# PA-VHF_60W.net
KiCad netlist of a schematic drawn in Altium Designer
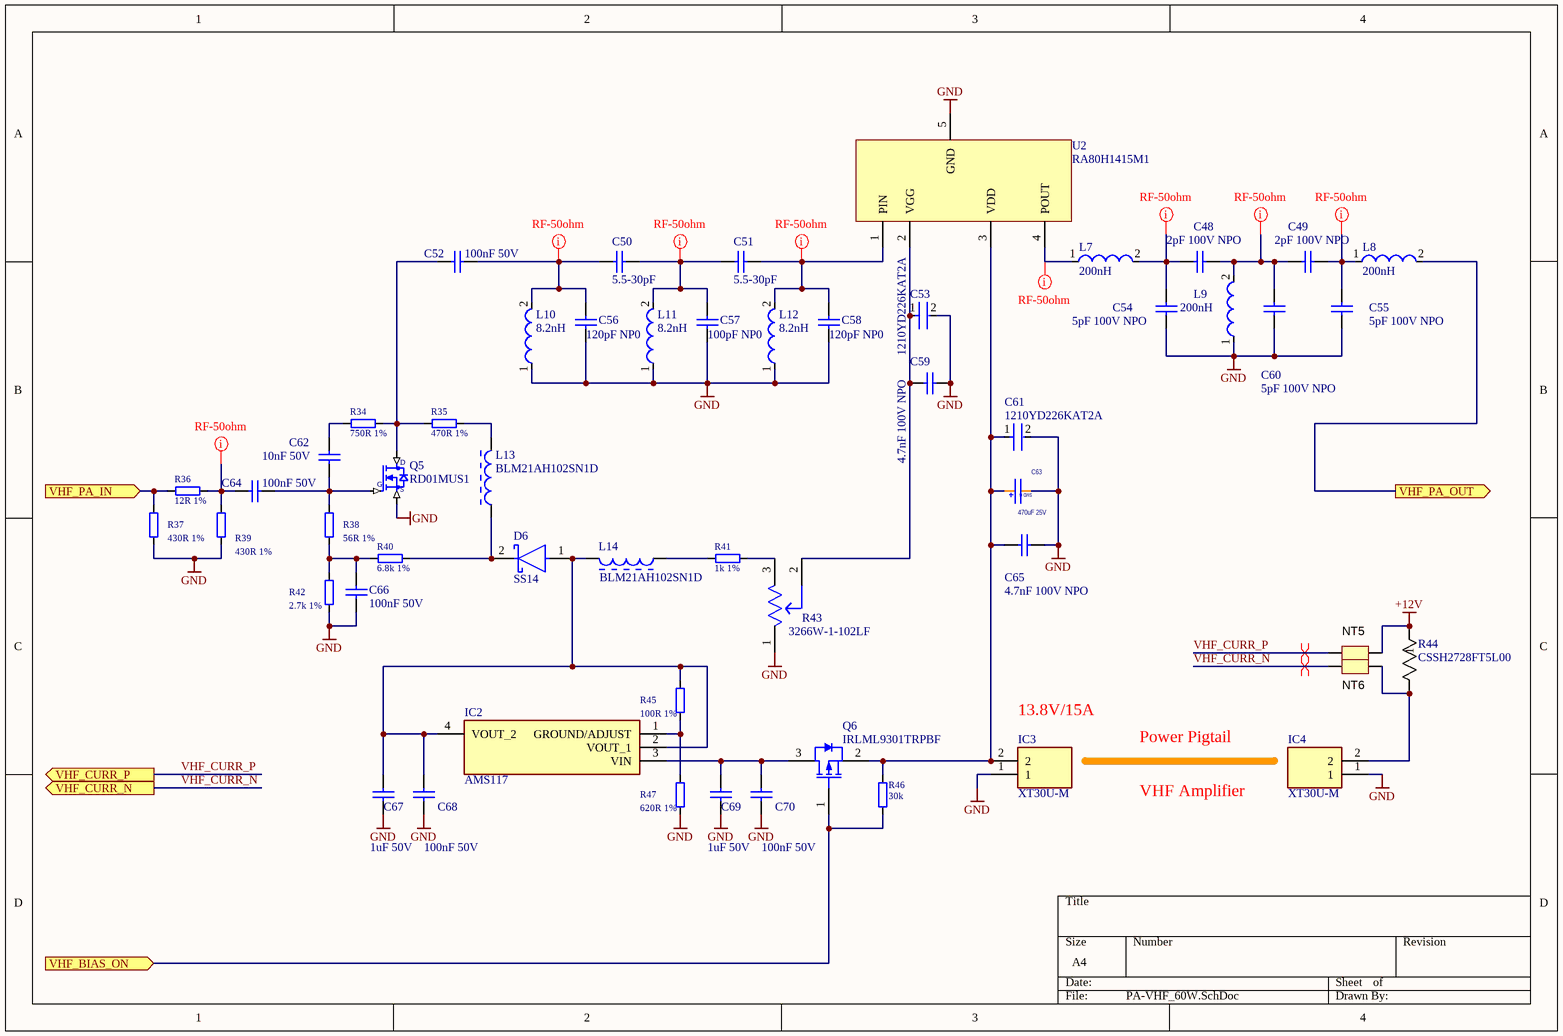
[diagram p0: PA-VHF_60W.SchDoc]

(export (version "E")
  (design (tool "Eeschema 10.0.6"))
  (components
    (comp (ref "C48")
      (value "2pF 100V NPO")
      (footprint "C-1206")
      (description "Ceramic Multilayer Capacitor")
      (libsource (lib "Hristo") (part "C semi"))
    )
    (comp (ref "C49")
      (value "2pF 100V NPO")
      (footprint "C-1206")
      (description "Ceramic Multilayer Capacitor")
      (libsource (lib "Hristo") (part "C semi"))
    )
    (comp (ref "C50")
      (value "5.5-30pF")
      (footprint "CAP-ADJ-SMD_L4.5-W3.2-L")
      (description "Ceramic Multilayer Capacitor")
      (fields (field (name "MANUFACTURER") "Yageo/Phycomp") (field (name "TOLERANCE") "±10%"))
      (libsource (lib "Hristo") (part "C semi"))
    )
    (comp (ref "C51")
      (value "5.5-30pF")
      (footprint "CAP-ADJ-SMD_L4.5-W3.2-L")
      (description "Ceramic Multilayer Capacitor")
      (fields (field (name "MANUFACTURER") "Yageo/Phycomp") (field (name "TOLERANCE") "±10%"))
      (libsource (lib "Hristo") (part "C semi"))
    )
    (comp (ref "C52")
      (value "100nF 50V")
      (footprint "C-0805")
      (description "Ceramic Multilayer Capacitor")
      (libsource (lib "Hristo") (part "C semi"))
    )
    (comp (ref "C53")
      (value "1210YD226KAT2A")
      (footprint "FP-1210-L_3_3_0_4-W_2_5_0-MFG")
      (description "General Purpose Ceramic Capacitor, 1210, 22uF, 10%, X5R, 15%, 16V")
      (fields (field (name "TOLERANCE") "10%") (field (name "VOLTAGE") "16V"))
      (libsource (lib "Altium Content Vault") (part "b4654b650e69147ec39a6b967a45e02"))
    )
    (comp (ref "C54")
      (value "5pF 100V NPO")
      (footprint "C-1206")
      (description "Ceramic Multilayer Capacitor")
      (libsource (lib "Hristo") (part "C semi"))
    )
    (comp (ref "C55")
      (value "5pF 100V NPO")
      (footprint "C-1206")
      (description "Ceramic Multilayer Capacitor")
      (libsource (lib "Hristo") (part "C semi"))
    )
    (comp (ref "C56")
      (value "120pF NP0")
      (footprint "C-0805")
      (description "Ceramic Multilayer Capacitor")
      (fields (field (name "MANUFACTURER") "Yageo/Phycomp") (field (name "TOLERANCE") "±10%"))
      (libsource (lib "Hristo") (part "C semi"))
    )
    (comp (ref "C57")
      (value "100pF NP0")
      (footprint "C-0805")
      (description "Ceramic Multilayer Capacitor")
      (fields (field (name "MANUFACTURER") "Yageo/Phycomp") (field (name "TOLERANCE") "±10%"))
      (libsource (lib "Hristo") (part "C semi"))
    )
    (comp (ref "C58")
      (value "120pF NP0")
      (footprint "C-0805")
      (description "Ceramic Multilayer Capacitor")
      (fields (field (name "MANUFACTURER") "Yageo/Phycomp") (field (name "TOLERANCE") "±10%"))
      (libsource (lib "Hristo") (part "C semi"))
    )
    (comp (ref "C59")
      (value "4.7nF 100V NPO")
      (footprint "C-1206")
      (description "Ceramic Multilayer Capacitor")
      (libsource (lib "Hristo") (part "C semi"))
    )
    (comp (ref "C60")
      (value "5pF 100V NPO")
      (footprint "C-1206")
      (description "Ceramic Multilayer Capacitor")
      (libsource (lib "Hristo") (part "C semi"))
    )
    (comp (ref "C61")
      (value "1210YD226KAT2A")
      (footprint "FP-1210-L_3_3_0_4-W_2_5_0-MFG")
      (description "General Purpose Ceramic Capacitor, 1210, 22uF, 10%, X5R, 15%, 16V")
      (fields (field (name "TOLERANCE") "10%") (field (name "VOLTAGE") "16V"))
      (libsource (lib "Altium Content Vault") (part "b4654b650e69147ec39a6b967a45e02"))
    )
    (comp (ref "C62")
      (value "10nF 50V")
      (footprint "C-0805")
      (description "Ceramic Multilayer Capacitor")
      (libsource (lib "Hristo") (part "C semi"))
    )
    (comp (ref "C63")
      (value "470uF 25V")
      (footprint "SMD-G-10X10.2")
      (description "CAP ALUM 470UF 20% 25V SMD")
      (fields
        (field (name "TOLERANCE") "±20 %")
        (field (name "VOLTAGE") "25V")
        (field (name "PUBLISHER") "Catcatcat Electronics")
      )
      (libsource (lib "CapacitorElectrolytic") (part "SMD-G 470uF 25V"))
    )
    (comp (ref "C64")
      (value "100nF 50V")
      (footprint "C-0805")
      (description "Ceramic Multilayer Capacitor")
      (libsource (lib "Hristo") (part "C semi"))
    )
    (comp (ref "C65")
      (value "4.7nF 100V NPO")
      (footprint "C-1206")
      (description "Ceramic Multilayer Capacitor")
      (libsource (lib "Hristo") (part "C semi"))
    )
    (comp (ref "C66")
      (value "100nF 50V")
      (footprint "C-0805")
      (description "Ceramic Multilayer Capacitor")
      (libsource (lib "Hristo") (part "C semi"))
    )
    (comp (ref "C67")
      (value "1uF 50V")
      (footprint "C-0805")
      (description "Ceramic Multilayer Capacitor")
      (libsource (lib "Hristo") (part "C semi"))
    )
    (comp (ref "C68")
      (value "100nF 50V")
      (footprint "C-0805")
      (description "Ceramic Multilayer Capacitor")
      (libsource (lib "Hristo") (part "C semi"))
    )
    (comp (ref "C69")
      (value "1uF 50V")
      (footprint "C-0805")
      (description "Ceramic Multilayer Capacitor")
      (libsource (lib "Hristo") (part "C semi"))
    )
    (comp (ref "C70")
      (value "100nF 50V")
      (footprint "C-0805")
      (description "Ceramic Multilayer Capacitor")
      (libsource (lib "Hristo") (part "C semi"))
    )
    (comp (ref "D6")
      (value "SS14")
      (footprint "FP-403AE-MFG")
      (description "DIODE SCHOTTKY 40V 1A SMA")
      (fields
        (field (name "MANUFACTURER") "ON Semiconductor")
        (field (name "OCTOPART") "https://octopart.com/ss14-on+semiconductor-29205033")
      )
      (libsource (lib "Altium Content Vault") (part "360ad2f4ac25a952324d13796385471"))
    )
    (comp (ref "IC2")
      (value "AMS117")
      (footprint "SamacSys:SOT229P700X180-4N")
      (description "Integrated Circuit")
      (libsource (lib "*") (part "AMS117"))
    )
    (comp (ref "IC3")
      (value "XT30U-M")
      (footprint "SamacSys:XT30UM")
      (description "Integrated Circuit")
      (libsource (lib "*") (part "XT30U-M"))
    )
    (comp (ref "IC4")
      (value "XT30U-M")
      (footprint "SamacSys:XT30UM")
      (description "Integrated Circuit")
      (libsource (lib "") (part "XT30U-M_1"))
    )
    (comp (ref "L7")
      (value "200nH")
      (footprint "AirCoil_200nH")
      (libsource (lib "Hristo") (part "RF_inductor"))
    )
    (comp (ref "L8")
      (value "200nH")
      (footprint "AirCoil_200nH")
      (libsource (lib "Hristo") (part "RF_inductor"))
    )
    (comp (ref "L9")
      (value "200nH")
      (footprint "AirCoil_200nH")
      (libsource (lib "Hristo") (part "RF_inductor"))
    )
    (comp (ref "L10") (value "8.2nH") (footprint "L-0805") (libsource (lib "Hristo") (part "RF_inductor")))
    (comp (ref "L11") (value "8.2nH") (footprint "L-0805") (libsource (lib "Hristo") (part "RF_inductor")))
    (comp (ref "L12") (value "8.2nH") (footprint "L-0805") (libsource (lib "Hristo") (part "RF_inductor")))
    (comp (ref "L13")
      (value "BLM21AH102SN1D")
      (footprint "INDC2013X105X50LL20T20")
      (description "Chip Bead, 1000 Ohm, +/- 25%, 200 mA, -55 to 85 degC, 2-Pin SMD, RoHS, Tape and Reel")
      (fields (field (name "MANUFACTURER") "Murata") (field (name "TOLERANCE") "25%"))
      (libsource (lib "Altium Content Vault") (part "IND-FB-2"))
    )
    (comp (ref "L14")
      (value "BLM21AH102SN1D")
      (footprint "INDC2013X105X50LL20T20")
      (description "Chip Bead, 1000 Ohm, +/- 25%, 200 mA, -55 to 85 degC, 2-Pin SMD, RoHS, Tape and Reel")
      (fields (field (name "MANUFACTURER") "Murata") (field (name "TOLERANCE") "25%"))
      (libsource (lib "Altium Content Vault") (part "IND-FB-2"))
    )
    (comp (ref "NT5")
      (value "Net-Tie")
      (footprint "Net-Tie_10mil")
      (description "Single point connection between nets.")
      (fields (field (name "SYMBOLCREATOR") "codlsc") (field (name "PUBLISHER") "Texas Instruments"))
      (libsource (lib "Hristo") (part "Net-Tie"))
    )
    (comp (ref "NT6")
      (value "Net-Tie")
      (footprint "Net-Tie_10mil")
      (description "Single point connection between nets.")
      (fields (field (name "SYMBOLCREATOR") "codlsc") (field (name "PUBLISHER") "Texas Instruments"))
      (libsource (lib "Hristo") (part "Net-Tie"))
    )
    (comp (ref "Q5")
      (value "RD01MUS1")
      (footprint "RD01MUS2_MTS")
      (libsource (lib "Hristo") (part "RD01MUS1"))
    )
    (comp (ref "Q6")
      (value "IRLML9301TRPBF")
      (footprint "INF-SOT-23-3_V")
      (description "HEXFET(R) Power MOSFET, 3.6 A, 30 V, -55 to 150 degC, 3-Pin SOT-23, RoHS, Tape and Reel")
      (fields (field (name "MANUFACTURER") "InfineonTechnologies"))
      (libsource (lib "Altium Content Vault") (part "PEMOS-GSD-3"))
    )
    (comp (ref "R34")
      (value "750R 1%")
      (footprint "R-0805")
      (description "Chip Resistor")
      (libsource (lib "Hristo") (part "RES semi"))
    )
    (comp (ref "R35")
      (value "470R 1%")
      (footprint "R-0805")
      (description "Chip Resistor")
      (libsource (lib "Hristo") (part "RES semi"))
    )
    (comp (ref "R36")
      (value "12R 1%")
      (footprint "R-0805")
      (description "Chip Resistor")
      (libsource (lib "Hristo") (part "RES semi"))
    )
    (comp (ref "R37")
      (value "430R 1%")
      (footprint "R-0805")
      (description "Chip Resistor")
      (libsource (lib "Hristo") (part "RES semi"))
    )
    (comp (ref "R38")
      (value "56R 1%")
      (footprint "R-0805")
      (description "Chip Resistor")
      (libsource (lib "Hristo") (part "RES semi"))
    )
    (comp (ref "R39")
      (value "430R 1%")
      (footprint "R-0805")
      (description "Chip Resistor")
      (libsource (lib "Hristo") (part "RES semi"))
    )
    (comp (ref "R40")
      (value "6.8k 1%")
      (footprint "R-0805")
      (description "Chip Resistor")
      (libsource (lib "Hristo") (part "RES semi"))
    )
    (comp (ref "R41")
      (value "1k 1%")
      (footprint "R-0805")
      (description "Chip Resistor")
      (libsource (lib "Hristo") (part "RES semi"))
    )
    (comp (ref "R42")
      (value "2.7k 1%")
      (footprint "R-0805")
      (description "Chip Resistor")
      (libsource (lib "Hristo") (part "RES semi"))
    )
    (comp (ref "R43")
      (value "3266W-1-102LF")
      (footprint "FP-3266W-MFG")
      (description "TRIMMER 1K OHM 0.25W PC PIN TOP")
      (fields
        (field (name "MANUFACTURER") "Bourns")
        (field (name "OCTOPART") "https://octopart.com/3266w-1-103lf-bourns-81445")
      )
      (libsource (lib "Altium Content Vault") (part "5aa38b60e553f01fbee9df648f8b81b"))
    )
    (comp (ref "R44")
      (value "CSSH2728FT5L00")
      (footprint "STA_CSSH2728_STP")
      (description "No Description Available")
      (fields (field (name "COPYRIGHT") "Copyright (C) 2022 Ultra Librarian. All rights reserved."))
      (libsource (lib "Hristo") (part "CSSH2728FT5L00"))
    )
    (comp (ref "R45")
      (value "100R 1%")
      (footprint "R-0805")
      (description "Chip Resistor")
      (libsource (lib "Hristo") (part "RES semi"))
    )
    (comp (ref "R46")
      (value "30k")
      (footprint "R-0603")
      (description "Chip Resistor")
      (fields (field (name "MANUFACTURER") "Yageo/Phycomp"))
      (libsource (lib "Hristo") (part "RES semi"))
    )
    (comp (ref "R47")
      (value "620R 1%")
      (footprint "R-0805")
      (description "Chip Resistor")
      (libsource (lib "Hristo") (part "RES semi"))
    )
    (comp (ref "U2")
      (value "RA80H1415M1")
      (footprint "RA80H1415M1")
      (libsource (lib "Sch") (part "RA80H1415M1"))
    )
  )
  (nets
    (net (code "1") (name "+12V") (class "Default")
      (node (ref "NT5") (pin "2") (pinfunction "2_2") (pintype "passive"))
      (node (ref "R44") (pin "1") (pinfunction "1_1") (pintype "passive"))
    )
    (net (code "2") (name "/VHF_BIAS_ON") (class "Default")
      (node (ref "Q6") (pin "1") (pinfunction "GATE_1") (pintype "passive"))
      (node (ref "R46") (pin "2") (pinfunction "2_2") (pintype "passive"))
    )
    (net (code "3") (name "/VHF_CURR_N") (class "Default")
      (node (ref "NT6") (pin "1") (pinfunction "1_1") (pintype "passive"))
    )
    (net (code "4") (name "/VHF_CURR_P") (class "Default")
      (node (ref "NT5") (pin "1") (pinfunction "1_1") (pintype "passive"))
    )
    (net (code "5") (name "/VHF_PA_IN") (class "Default")
      (node (ref "R36") (pin "1") (pinfunction "1_1") (pintype "passive"))
      (node (ref "R37") (pin "2") (pinfunction "2_2") (pintype "passive"))
    )
    (net (code "6") (name "/VHF_PA_OUT") (class "Default")
      (node (ref "L8") (pin "2") (pinfunction "2_2") (pintype "passive"))
    )
    (net (code "7") (name "GND") (class "Default")
      (node (ref "C53") (pin "2") (pinfunction "2_2") (pintype "passive"))
      (node (ref "C54") (pin "1") (pinfunction "1_1") (pintype "passive"))
      (node (ref "C55") (pin "1") (pinfunction "1_1") (pintype "passive"))
      (node (ref "C56") (pin "2") (pinfunction "2_2") (pintype "passive"))
      (node (ref "C57") (pin "2") (pinfunction "2_2") (pintype "passive"))
      (node (ref "C58") (pin "2") (pinfunction "2_2") (pintype "passive"))
      (node (ref "C59") (pin "2") (pinfunction "2_2") (pintype "passive"))
      (node (ref "C60") (pin "1") (pinfunction "1_1") (pintype "passive"))
      (node (ref "C61") (pin "2") (pinfunction "2_2") (pintype "passive"))
      (node (ref "C63") (pin "2") (pinfunction "2_2") (pintype "passive"))
      (node (ref "C65") (pin "2") (pinfunction "2_2") (pintype "passive"))
      (node (ref "C66") (pin "1") (pinfunction "1_1") (pintype "passive"))
      (node (ref "C67") (pin "1") (pinfunction "1_1") (pintype "passive"))
      (node (ref "C68") (pin "1") (pinfunction "1_1") (pintype "passive"))
      (node (ref "C69") (pin "1") (pinfunction "1_1") (pintype "passive"))
      (node (ref "C70") (pin "1") (pinfunction "1_1") (pintype "passive"))
      (node (ref "IC3") (pin "1") (pinfunction "1_1") (pintype "passive"))
      (node (ref "IC4") (pin "1") (pinfunction "1_1") (pintype "passive"))
      (node (ref "L10") (pin "1") (pinfunction "1_1") (pintype "passive"))
      (node (ref "L11") (pin "1") (pinfunction "1_1") (pintype "passive"))
      (node (ref "L12") (pin "1") (pinfunction "1_1") (pintype "passive"))
      (node (ref "L9") (pin "1") (pinfunction "1_1") (pintype "passive"))
      (node (ref "Q5") (pin "1") (pinfunction "S_1") (pintype "input"))
      (node (ref "R37") (pin "1") (pinfunction "1_1") (pintype "passive"))
      (node (ref "R39") (pin "1") (pinfunction "1_1") (pintype "passive"))
      (node (ref "R42") (pin "1") (pinfunction "1_1") (pintype "passive"))
      (node (ref "R43") (pin "1") (pinfunction "CCW_1") (pintype "passive"))
      (node (ref "R47") (pin "1") (pinfunction "1_1") (pintype "passive"))
      (node (ref "U2") (pin "5") (pinfunction "GND_5") (pintype "power_in"))
    )
    (net (code "8") (name "Net-(C48-Pad1)") (class "Default")
      (node (ref "C48") (pin "1") (pinfunction "1_1") (pintype "passive"))
      (node (ref "C54") (pin "2") (pinfunction "2_2") (pintype "passive"))
      (node (ref "L7") (pin "2") (pinfunction "2_2") (pintype "passive"))
    )
    (net (code "9") (name "Net-(C48-Pad2)") (class "Default")
      (node (ref "C48") (pin "2") (pinfunction "2_2") (pintype "passive"))
      (node (ref "C49") (pin "1") (pinfunction "1_1") (pintype "passive"))
      (node (ref "C60") (pin "2") (pinfunction "2_2") (pintype "passive"))
      (node (ref "L9") (pin "2") (pinfunction "2_2") (pintype "passive"))
    )
    (net (code "10") (name "Net-(C49-Pad2)") (class "Default")
      (node (ref "C49") (pin "2") (pinfunction "2_2") (pintype "passive"))
      (node (ref "C55") (pin "2") (pinfunction "2_2") (pintype "passive"))
      (node (ref "L8") (pin "1") (pinfunction "1_1") (pintype "passive"))
    )
    (net (code "11") (name "Net-(C50-Pad1)") (class "Default")
      (node (ref "C50") (pin "1") (pinfunction "1_1") (pintype "passive"))
      (node (ref "C52") (pin "2") (pinfunction "2_2") (pintype "passive"))
      (node (ref "C56") (pin "1") (pinfunction "1_1") (pintype "passive"))
      (node (ref "L10") (pin "2") (pinfunction "2_2") (pintype "passive"))
    )
    (net (code "12") (name "Net-(C50-Pad2)") (class "Default")
      (node (ref "C50") (pin "2") (pinfunction "2_2") (pintype "passive"))
      (node (ref "C51") (pin "1") (pinfunction "1_1") (pintype "passive"))
      (node (ref "C57") (pin "1") (pinfunction "1_1") (pintype "passive"))
      (node (ref "L11") (pin "2") (pinfunction "2_2") (pintype "passive"))
    )
    (net (code "13") (name "Net-(C62-Pad1)") (class "Default")
      (node (ref "C62") (pin "1") (pinfunction "1_1") (pintype "passive"))
      (node (ref "C64") (pin "2") (pinfunction "2_2") (pintype "passive"))
      (node (ref "Q5") (pin "2") (pintype "input"))
      (node (ref "R38") (pin "2") (pinfunction "2_2") (pintype "passive"))
    )
    (net (code "14") (name "Net-(C62-Pad2)") (class "Default")
      (node (ref "C62") (pin "2") (pinfunction "2_2") (pintype "passive"))
      (node (ref "R34") (pin "2") (pinfunction "2_2") (pintype "passive"))
    )
    (net (code "15") (name "Net-(C64-Pad1)") (class "Default")
      (node (ref "C64") (pin "1") (pinfunction "1_1") (pintype "passive"))
      (node (ref "R36") (pin "2") (pinfunction "2_2") (pintype "passive"))
      (node (ref "R39") (pin "2") (pinfunction "2_2") (pintype "passive"))
    )
    (net (code "16") (name "Net-(C66-Pad2)") (class "Default")
      (node (ref "C66") (pin "2") (pinfunction "2_2") (pintype "passive"))
      (node (ref "R38") (pin "1") (pinfunction "1_1") (pintype "passive"))
      (node (ref "R40") (pin "2") (pinfunction "2_2") (pintype "passive"))
      (node (ref "R42") (pin "2") (pinfunction "2_2") (pintype "passive"))
    )
    (net (code "17") (name "Net-(D6-A)") (class "Default")
      (node (ref "C67") (pin "2") (pinfunction "2_2") (pintype "passive"))
      (node (ref "C68") (pin "2") (pinfunction "2_2") (pintype "passive"))
      (node (ref "D6") (pin "1") (pinfunction "A_1") (pintype "passive"))
      (node (ref "IC2") (pin "2") (pinfunction "VOUT_1_2") (pintype "passive"))
      (node (ref "IC2") (pin "4") (pinfunction "VOUT_2_4") (pintype "passive"))
      (node (ref "L14") (pin "2") (pinfunction "2_2") (pintype "passive"))
      (node (ref "R45") (pin "2") (pinfunction "2_2") (pintype "passive"))
    )
    (net (code "18") (name "Net-(D6-C)") (class "Default")
      (node (ref "D6") (pin "2") (pinfunction "C_2") (pintype "passive"))
      (node (ref "L13") (pin "1") (pinfunction "1_1") (pintype "passive"))
      (node (ref "R40") (pin "1") (pinfunction "1_1") (pintype "passive"))
    )
    (net (code "19") (name "Net-(IC2-GROUND{slash}ADJUST)") (class "Default")
      (node (ref "IC2") (pin "1") (pinfunction "GROUND/ADJUST_1") (pintype "passive"))
      (node (ref "R45") (pin "1") (pinfunction "1_1") (pintype "passive"))
      (node (ref "R47") (pin "2") (pinfunction "2_2") (pintype "passive"))
    )
    (net (code "20") (name "Net-(IC2-VIN)") (class "Default")
      (node (ref "C69") (pin "2") (pinfunction "2_2") (pintype "passive"))
      (node (ref "C70") (pin "2") (pinfunction "2_2") (pintype "passive"))
      (node (ref "IC2") (pin "3") (pinfunction "VIN_3") (pintype "passive"))
      (node (ref "Q6") (pin "3") (pinfunction "DRAIN_3") (pintype "passive"))
    )
    (net (code "21") (name "Net-(IC4-Pad2)") (class "Default")
      (node (ref "IC4") (pin "2") (pinfunction "2_2") (pintype "passive"))
      (node (ref "NT6") (pin "2") (pinfunction "2_2") (pintype "passive"))
      (node (ref "R44") (pin "2") (pinfunction "2_2") (pintype "passive"))
    )
    (net (code "22") (name "Net-(L13-Pad2)") (class "Default")
      (node (ref "L13") (pin "2") (pinfunction "2_2") (pintype "passive"))
      (node (ref "R35") (pin "1") (pinfunction "1_1") (pintype "passive"))
    )
    (net (code "23") (name "Net-(L14-Pad1)") (class "Default")
      (node (ref "L14") (pin "1") (pinfunction "1_1") (pintype "passive"))
      (node (ref "R41") (pin "2") (pinfunction "2_2") (pintype "passive"))
    )
    (net (code "24") (name "Net-(Q5-D)") (class "Default")
      (node (ref "C52") (pin "1") (pinfunction "1_1") (pintype "passive"))
      (node (ref "Q5") (pin "3") (pinfunction "D_3") (pintype "input"))
      (node (ref "R34") (pin "1") (pinfunction "1_1") (pintype "passive"))
      (node (ref "R35") (pin "2") (pinfunction "2_2") (pintype "passive"))
    )
    (net (code "25") (name "Net-(Q6-SOURCE)") (class "Default")
      (node (ref "C61") (pin "1") (pinfunction "1_1") (pintype "passive"))
      (node (ref "C63") (pin "1") (pinfunction "1_1") (pintype "passive"))
      (node (ref "C65") (pin "1") (pinfunction "1_1") (pintype "passive"))
      (node (ref "IC3") (pin "2") (pinfunction "2_2") (pintype "passive"))
      (node (ref "Q6") (pin "2") (pinfunction "SOURCE_2") (pintype "passive"))
      (node (ref "R46") (pin "1") (pinfunction "1_1") (pintype "passive"))
      (node (ref "U2") (pin "3") (pinfunction "VDD_3") (pintype "power_in"))
    )
    (net (code "26") (name "Net-(R43-CW)") (class "Default")
      (node (ref "R41") (pin "1") (pinfunction "1_1") (pintype "passive"))
      (node (ref "R43") (pin "3") (pinfunction "CW_3") (pintype "passive"))
    )
    (net (code "27") (name "Net-(R43-WIPER)") (class "Default")
      (node (ref "C53") (pin "1") (pinfunction "1_1") (pintype "passive"))
      (node (ref "C59") (pin "1") (pinfunction "1_1") (pintype "passive"))
      (node (ref "R43") (pin "2") (pinfunction "WIPER_2") (pintype "passive"))
      (node (ref "U2") (pin "2") (pinfunction "VGG_2") (pintype "power_in"))
    )
    (net (code "28") (name "Net-(U2-PIN)") (class "Default")
      (node (ref "C51") (pin "2") (pinfunction "2_2") (pintype "passive"))
      (node (ref "C58") (pin "1") (pinfunction "1_1") (pintype "passive"))
      (node (ref "L12") (pin "2") (pinfunction "2_2") (pintype "passive"))
      (node (ref "U2") (pin "1") (pinfunction "PIN_1") (pintype "power_in"))
    )
    (net (code "29") (name "Net-(U2-POUT)") (class "Default")
      (node (ref "L7") (pin "1") (pinfunction "1_1") (pintype "passive"))
      (node (ref "U2") (pin "4") (pinfunction "POUT_4") (pintype "power_in"))
    )
  )
)
